# MCU.net
KiCad netlist of a schematic drawn in Altium Designer
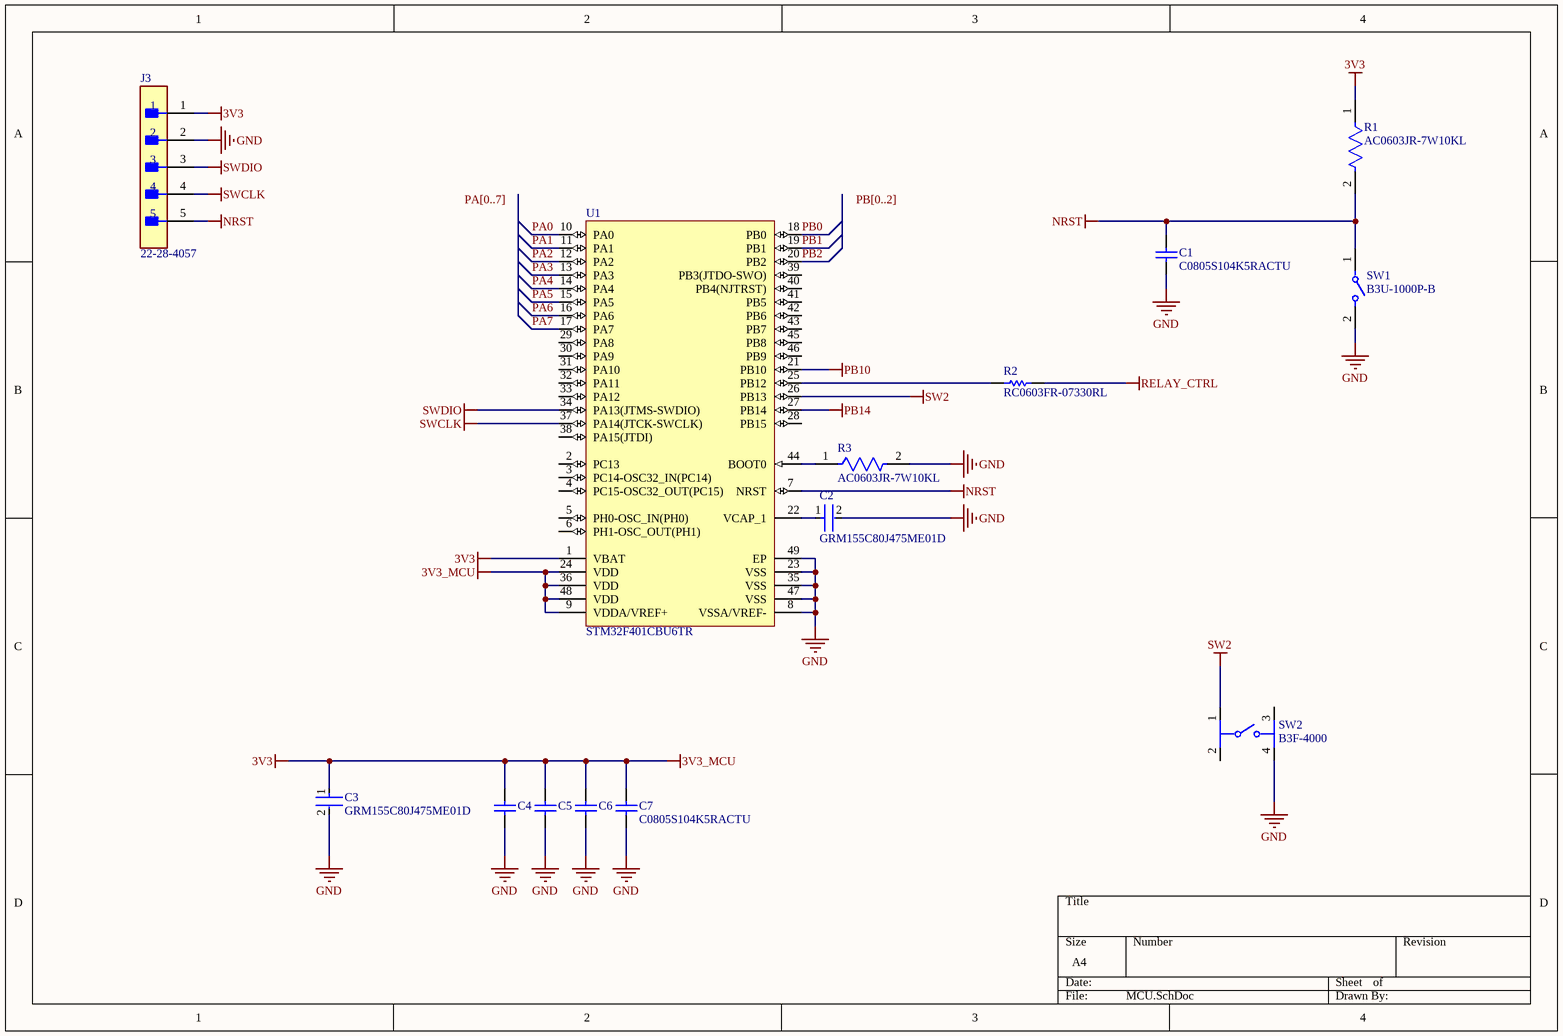
[diagram p0: MCU.SchDoc]

(export (version "E")
  (design (tool "Eeschema 10.0.6"))
  (components
    (comp (ref "C1")
      (value "C0805S104K5RACTU")
      (footprint "CAPC2013X145X50NL20T25")
      (description "100 nF 50 VDC X7R 10 % 0805")
      (fields (field (name "MANUFACTURER") "Kemet"))
      (libsource (lib "Altium Content Vault") (part "CAP"))
    )
    (comp (ref "C2")
      (value "GRM155C80J475ME01D")
      (footprint "FP-GRM155-0_2-MFG")
      (description "4.7 uF\r\nGRM155C80J475ME01D")
      (libsource (lib "Altium Content Vault") (part "b4654b650e69147ec39a6b967a45e02"))
    )
    (comp (ref "C3")
      (value "GRM155C80J475ME01D")
      (footprint "FP-GRM155-0_2-MFG")
      (description "4.7 uF\r\nGRM155C80J475ME01D")
      (libsource (lib "Altium Content Vault") (part "b4654b650e69147ec39a6b967a45e02"))
    )
    (comp (ref "C4")
      (value "C0805S104K5RACTU")
      (footprint "CAPC2013X145X50NL20T25")
      (description "100 nF 50 VDC X7R 10 % 0805")
      (fields (field (name "MANUFACTURER") "Kemet"))
      (libsource (lib "Altium Content Vault") (part "CAP"))
    )
    (comp (ref "C5")
      (value "C0805S104K5RACTU")
      (footprint "CAPC2013X145X50NL20T25")
      (description "100 nF 50 VDC X7R 10 % 0805")
      (fields (field (name "MANUFACTURER") "Kemet"))
      (libsource (lib "Altium Content Vault") (part "CAP"))
    )
    (comp (ref "C6")
      (value "C0805S104K5RACTU")
      (footprint "CAPC2013X145X50NL20T25")
      (description "100 nF 50 VDC X7R 10 % 0805")
      (fields (field (name "MANUFACTURER") "Kemet"))
      (libsource (lib "Altium Content Vault") (part "CAP"))
    )
    (comp (ref "C7")
      (value "C0805S104K5RACTU")
      (footprint "CAPC2013X145X50NL20T25")
      (description "100 nF 50 VDC X7R 10 % 0805")
      (fields (field (name "MANUFACTURER") "Kemet"))
      (libsource (lib "Altium Content Vault") (part "CAP"))
    )
    (comp (ref "J3")
      (value "22-28-4057")
      (footprint "FP-22-28-4057-MFG")
      (description "KK 100 HDR ASSY BKWY 05 CKT 30 S")
      (libsource (lib "Altium Content Vault") (part "bf93c07fd2649a848d0ec8585582aab"))
    )
    (comp (ref "R1")
      (value "AC0603JR-7W10KL")
      (footprint "FP-AC0603-IPC_A")
      (description "RES 10kΩ 5.00% 0.2W 0603")
      (libsource (lib "Altium Content Vault") (part "1029c3af85768c4190bb7ad29bc67b5"))
    )
    (comp (ref "R2")
      (value "RC0603FR-07330RL")
      (footprint "RESC1608X55X25NL10T15")
      (description "Chip Resistor, 330 Ohm, +/- 1%, 0.1 W, -55 to 155 degC, 0603 (1608 Metric), RoHS, Tape and Reel")
      (fields (field (name "TOLERANCE") "10%"))
      (libsource (lib "Altium Content Vault") (part "RES-2"))
    )
    (comp (ref "R3")
      (value "AC0603JR-7W10KL")
      (footprint "FP-AC0603-IPC_A")
      (description "RES 10kΩ 5.00% 0.2W 0603")
      (libsource (lib "Altium Content Vault") (part "1029c3af85768c4190bb7ad29bc67b5"))
    )
    (comp (ref "SW1")
      (value "B3U-1000P-B")
      (footprint "FP-B3U-1000P-B-MFG")
      (description "Tactile Switch SPST-NO Top Actuated Surface Mount")
      (fields (field (name "OCTOPART") "https://octopart.com/b3u-1000p-b-omron-1057356"))
      (libsource (lib "Altium Content Vault") (part "bb27bde45df87f1f469753f287ef5ae"))
    )
    (comp (ref "SW2")
      (value "B3F-4000")
      (footprint "FP-B3F-4000-MFG")
      (description "SWITCH TACTILE SPST-NO 0.05A 24V")
      (fields
        (field (name "MANUFACTURER") "Omron")
        (field (name "OCTOPART") "https://octopart.com/b3f-4000-omron-22510")
      )
      (libsource (lib "Altium Content Vault") (part "b8895f3f4cefb76e1819d2863dba89b"))
    )
    (comp (ref "U1")
      (value "STM32F401CBU6TR")
      (footprint "STM-UFQFPN48_L")
      (libsource (lib "Altium Content Vault") (part "MC-ARM-STM32F401-UFQFPN48"))
    )
  )
  (nets
    (net (code "1") (name "/PA0") (class "Default")
      (node (ref "U1") (pin "10") (pinfunction "PA0_10") (pintype "bidirectional"))
    )
    (net (code "2") (name "/PA1") (class "Default")
      (node (ref "U1") (pin "11") (pinfunction "PA1_11") (pintype "bidirectional"))
    )
    (net (code "3") (name "/PA2") (class "Default")
      (node (ref "U1") (pin "12") (pinfunction "PA2_12") (pintype "bidirectional"))
    )
    (net (code "4") (name "/PA3") (class "Default")
      (node (ref "U1") (pin "13") (pinfunction "PA3_13") (pintype "bidirectional"))
    )
    (net (code "5") (name "/PA4") (class "Default")
      (node (ref "U1") (pin "14") (pinfunction "PA4_14") (pintype "bidirectional"))
    )
    (net (code "6") (name "/PA5") (class "Default")
      (node (ref "U1") (pin "15") (pinfunction "PA5_15") (pintype "bidirectional"))
    )
    (net (code "7") (name "/PA6") (class "Default")
      (node (ref "U1") (pin "16") (pinfunction "PA6_16") (pintype "bidirectional"))
    )
    (net (code "8") (name "/PA7") (class "Default")
      (node (ref "U1") (pin "17") (pinfunction "PA7_17") (pintype "bidirectional"))
    )
    (net (code "10") (name "/PB0") (class "Default")
      (node (ref "U1") (pin "18") (pinfunction "PB0_18") (pintype "bidirectional"))
    )
    (net (code "11") (name "/PB1") (class "Default")
      (node (ref "U1") (pin "19") (pinfunction "PB1_19") (pintype "bidirectional"))
    )
    (net (code "12") (name "/PB2") (class "Default")
      (node (ref "U1") (pin "20") (pinfunction "PB2_20") (pintype "bidirectional"))
    )
    (net (code "14") (name "3V3") (class "Default")
      (node (ref "C3") (pin "1") (pinfunction "1_1") (pintype "passive"))
      (node (ref "C4") (pin "2") (pinfunction "2_2") (pintype "passive"))
      (node (ref "C5") (pin "2") (pinfunction "2_2") (pintype "passive"))
      (node (ref "C6") (pin "2") (pinfunction "2_2") (pintype "passive"))
      (node (ref "C7") (pin "2") (pinfunction "2_2") (pintype "passive"))
      (node (ref "J3") (pin "1") (pinfunction "1_1") (pintype "passive"))
      (node (ref "R1") (pin "1") (pinfunction "1_1") (pintype "passive"))
      (node (ref "U1") (pin "1") (pinfunction "VBAT_1") (pintype "power_in"))
      (node (ref "U1") (pin "24") (pinfunction "VDD_24") (pintype "power_in"))
      (node (ref "U1") (pin "36") (pinfunction "VDD_36") (pintype "power_in"))
      (node (ref "U1") (pin "48") (pinfunction "VDD_48") (pintype "power_in"))
      (node (ref "U1") (pin "9") (pinfunction "VDDA/VREF+_9") (pintype "power_in"))
    )
    (net (code "15") (name "GND") (class "Default")
      (node (ref "C1") (pin "1") (pinfunction "1_1") (pintype "passive"))
      (node (ref "C2") (pin "2") (pinfunction "2_2") (pintype "passive"))
      (node (ref "C3") (pin "2") (pinfunction "2_2") (pintype "passive"))
      (node (ref "C4") (pin "1") (pinfunction "1_1") (pintype "passive"))
      (node (ref "C5") (pin "1") (pinfunction "1_1") (pintype "passive"))
      (node (ref "C6") (pin "1") (pinfunction "1_1") (pintype "passive"))
      (node (ref "C7") (pin "1") (pinfunction "1_1") (pintype "passive"))
      (node (ref "J3") (pin "2") (pinfunction "2_2") (pintype "passive"))
      (node (ref "R3") (pin "2") (pinfunction "2_2") (pintype "passive"))
      (node (ref "SW1") (pin "2") (pinfunction "2_2") (pintype "passive"))
      (node (ref "SW2") (pin "4") (pinfunction "4_4") (pintype "passive"))
      (node (ref "U1") (pin "23") (pinfunction "VSS_23") (pintype "power_in"))
      (node (ref "U1") (pin "35") (pinfunction "VSS_35") (pintype "power_in"))
      (node (ref "U1") (pin "47") (pinfunction "VSS_47") (pintype "power_in"))
      (node (ref "U1") (pin "49") (pinfunction "EP_49") (pintype "power_in"))
      (node (ref "U1") (pin "8") (pinfunction "VSSA/VREF-_8") (pintype "power_in"))
    )
    (net (code "16") (name "NRST") (class "Default")
      (node (ref "C1") (pin "2") (pinfunction "2_2") (pintype "passive"))
      (node (ref "J3") (pin "5") (pinfunction "5_5") (pintype "passive"))
      (node (ref "R1") (pin "2") (pinfunction "2_2") (pintype "passive"))
      (node (ref "SW1") (pin "1") (pinfunction "1_1") (pintype "passive"))
      (node (ref "U1") (pin "7") (pinfunction "NRST_7") (pintype "bidirectional"))
    )
    (net (code "17") (name "Net-(U1-BOOT0)") (class "Default")
      (node (ref "R3") (pin "1") (pinfunction "1_1") (pintype "passive"))
      (node (ref "U1") (pin "44") (pinfunction "BOOT0_44") (pintype "input"))
    )
    (net (code "18") (name "Net-(U1-PB12)") (class "Default")
      (node (ref "R2") (pin "1") (pinfunction "1_1") (pintype "passive"))
      (node (ref "U1") (pin "25") (pinfunction "PB12_25") (pintype "bidirectional"))
    )
    (net (code "19") (name "Net-(U1-VCAP_1)") (class "Default")
      (node (ref "C2") (pin "1") (pinfunction "1_1") (pintype "passive"))
      (node (ref "U1") (pin "22") (pinfunction "VCAP_1_22") (pintype "passive"))
    )
    (net (code "20") (name "PB10") (class "Default")
      (node (ref "U1") (pin "21") (pinfunction "PB10_21") (pintype "bidirectional"))
    )
    (net (code "21") (name "PB14") (class "Default")
      (node (ref "U1") (pin "27") (pinfunction "PB14_27") (pintype "bidirectional"))
    )
    (net (code "22") (name "RELAY_CTRL") (class "Default")
      (node (ref "R2") (pin "2") (pinfunction "2_2") (pintype "passive"))
    )
    (net (code "23") (name "SW2") (class "Default")
      (node (ref "SW2") (pin "1") (pinfunction "1_1") (pintype "passive"))
      (node (ref "U1") (pin "26") (pinfunction "PB13_26") (pintype "bidirectional"))
    )
    (net (code "24") (name "SWCLK") (class "Default")
      (node (ref "J3") (pin "4") (pinfunction "4_4") (pintype "passive"))
      (node (ref "U1") (pin "37") (pinfunction "PA14(JTCK-SWCLK)_37") (pintype "bidirectional"))
    )
    (net (code "25") (name "SWDIO") (class "Default")
      (node (ref "J3") (pin "3") (pinfunction "3_3") (pintype "passive"))
      (node (ref "U1") (pin "34") (pinfunction "PA13(JTMS-SWDIO)_34") (pintype "bidirectional"))
    )
    (net (code "26") (name "unconnected-(SW2-Pad2)") (class "Default")
      (node (ref "SW2") (pin "2") (pinfunction "2_2") (pintype "passive"))
    )
    (net (code "27") (name "unconnected-(SW2-Pad3)") (class "Default")
      (node (ref "SW2") (pin "3") (pinfunction "3_3") (pintype "passive"))
    )
    (net (code "28") (name "unconnected-(U1-PA8-Pad29)") (class "Default")
      (node (ref "U1") (pin "29") (pinfunction "PA8_29") (pintype "bidirectional"))
    )
    (net (code "29") (name "unconnected-(U1-PA9-Pad30)") (class "Default")
      (node (ref "U1") (pin "30") (pinfunction "PA9_30") (pintype "bidirectional"))
    )
    (net (code "30") (name "unconnected-(U1-PA10-Pad31)") (class "Default")
      (node (ref "U1") (pin "31") (pinfunction "PA10_31") (pintype "bidirectional"))
    )
    (net (code "31") (name "unconnected-(U1-PA11-Pad32)") (class "Default")
      (node (ref "U1") (pin "32") (pinfunction "PA11_32") (pintype "bidirectional"))
    )
    (net (code "32") (name "unconnected-(U1-PA12-Pad33)") (class "Default")
      (node (ref "U1") (pin "33") (pinfunction "PA12_33") (pintype "bidirectional"))
    )
    (net (code "33") (name "unconnected-(U1-PA15(JTDI)-Pad38)") (class "Default")
      (node (ref "U1") (pin "38") (pinfunction "PA15(JTDI)_38") (pintype "bidirectional"))
    )
    (net (code "34") (name "unconnected-(U1-PB3(JTDO-SWO)-Pad39)") (class "Default")
      (node (ref "U1") (pin "39") (pinfunction "PB3(JTDO-SWO)_39") (pintype "bidirectional"))
    )
    (net (code "35") (name "unconnected-(U1-PB4(NJTRST)-Pad40)") (class "Default")
      (node (ref "U1") (pin "40") (pinfunction "PB4(NJTRST)_40") (pintype "bidirectional"))
    )
    (net (code "36") (name "unconnected-(U1-PB5-Pad41)") (class "Default")
      (node (ref "U1") (pin "41") (pinfunction "PB5_41") (pintype "bidirectional"))
    )
    (net (code "37") (name "unconnected-(U1-PB6-Pad42)") (class "Default")
      (node (ref "U1") (pin "42") (pinfunction "PB6_42") (pintype "bidirectional"))
    )
    (net (code "38") (name "unconnected-(U1-PB7-Pad43)") (class "Default")
      (node (ref "U1") (pin "43") (pinfunction "PB7_43") (pintype "bidirectional"))
    )
    (net (code "39") (name "unconnected-(U1-PB8-Pad45)") (class "Default")
      (node (ref "U1") (pin "45") (pinfunction "PB8_45") (pintype "bidirectional"))
    )
    (net (code "40") (name "unconnected-(U1-PB9-Pad46)") (class "Default")
      (node (ref "U1") (pin "46") (pinfunction "PB9_46") (pintype "bidirectional"))
    )
    (net (code "41") (name "unconnected-(U1-PB15-Pad28)") (class "Default")
      (node (ref "U1") (pin "28") (pinfunction "PB15_28") (pintype "bidirectional"))
    )
    (net (code "42") (name "unconnected-(U1-PC13-Pad2)") (class "Default")
      (node (ref "U1") (pin "2") (pinfunction "PC13_2") (pintype "bidirectional"))
    )
    (net (code "43") (name "unconnected-(U1-PC14-OSC32_IN(PC14)-Pad3)") (class "Default")
      (node (ref "U1") (pin "3") (pinfunction "PC14-OSC32_IN(PC14)_3") (pintype "bidirectional"))
    )
    (net (code "44") (name "unconnected-(U1-PC15-OSC32_OUT(PC15)-Pad4)") (class "Default")
      (node (ref "U1") (pin "4") (pinfunction "PC15-OSC32_OUT(PC15)_4") (pintype "bidirectional"))
    )
    (net (code "45") (name "unconnected-(U1-PH0-OSC_IN(PH0)-Pad5)") (class "Default")
      (node (ref "U1") (pin "5") (pinfunction "PH0-OSC_IN(PH0)_5") (pintype "bidirectional"))
    )
    (net (code "46") (name "unconnected-(U1-PH1-OSC_OUT(PH1)-Pad6)") (class "Default")
      (node (ref "U1") (pin "6") (pinfunction "PH1-OSC_OUT(PH1)_6") (pintype "bidirectional"))
    )
  )
)
